# ME433_2017_1.net
KiCad netlist of a schematic drawn in EAGLE
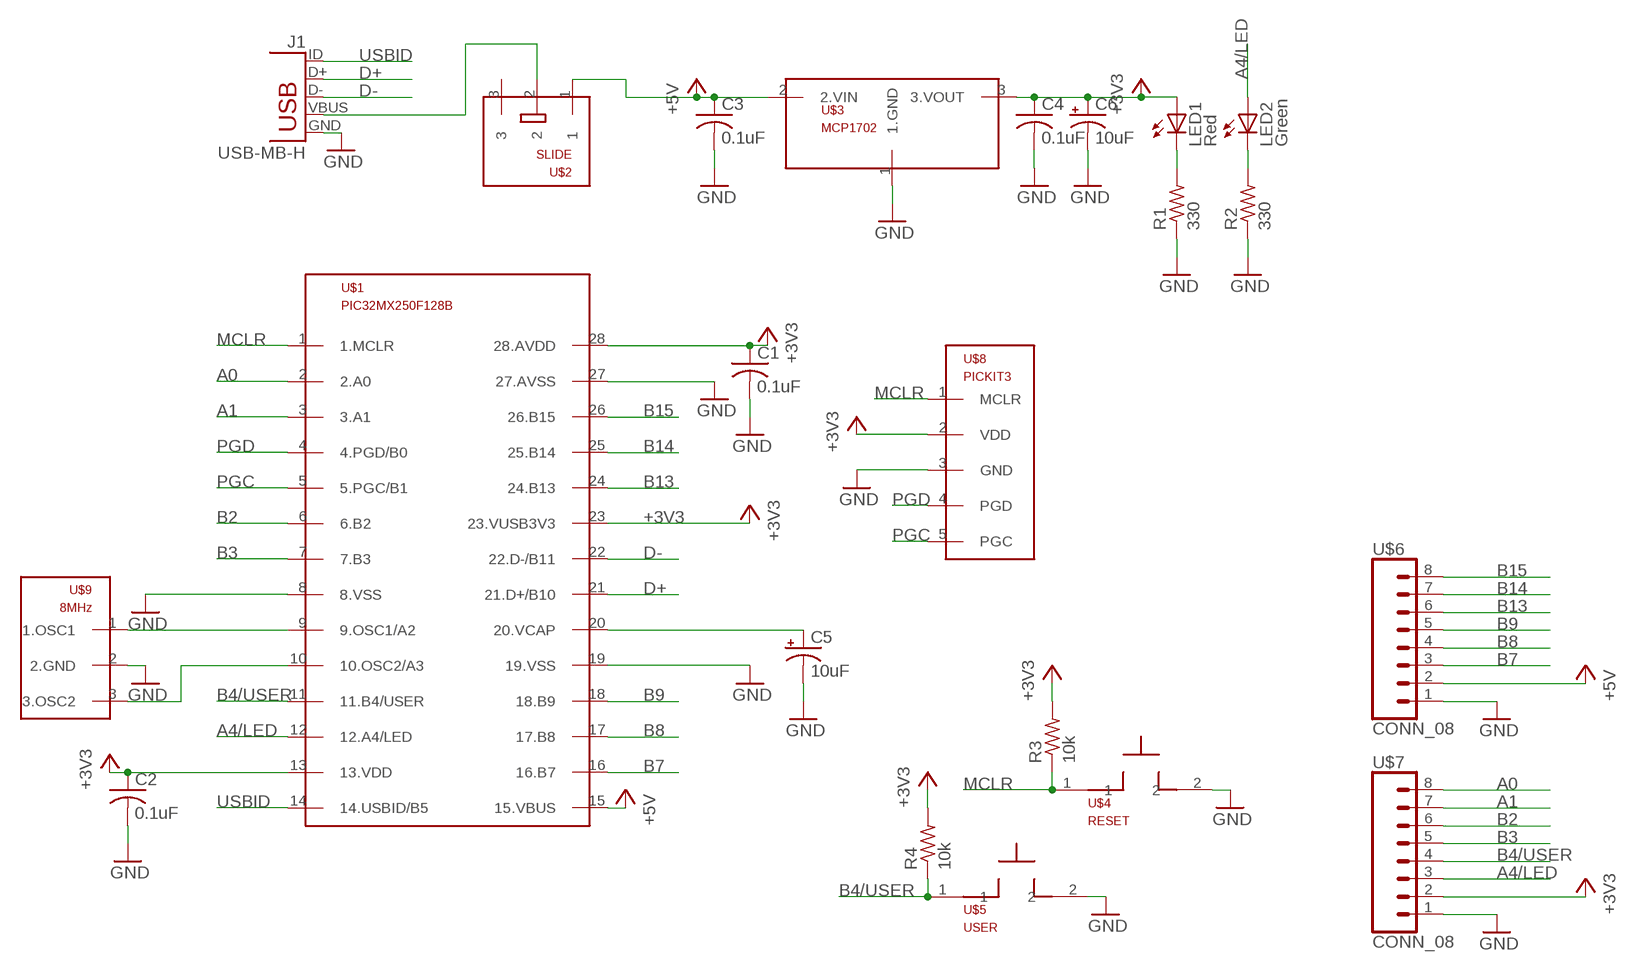
[diagram p0: schematic, sheet 1]

(export (version "E")
  (design (tool "Eeschema 10.0.6"))
  (components
    (comp (ref "C1")
      (value "0.1uF")
      (footprint "eagle-import:C025-025X050")
      (libsource (lib "eagle-import") (part "C-US025-025X050"))
    )
    (comp (ref "C2")
      (value "0.1uF")
      (footprint "eagle-import:C025-025X050")
      (libsource (lib "eagle-import") (part "C-US025-025X050"))
    )
    (comp (ref "C3")
      (value "0.1uF")
      (footprint "eagle-import:C025-025X050")
      (libsource (lib "eagle-import") (part "C-US025-025X050"))
    )
    (comp (ref "C4")
      (value "0.1uF")
      (footprint "eagle-import:C025-025X050")
      (libsource (lib "eagle-import") (part "C-US025-025X050"))
    )
    (comp (ref "C5")
      (value "10uF")
      (footprint "eagle-import:B45181B")
      (libsource (lib "eagle-import") (part "CPOL-USB45181B"))
    )
    (comp (ref "C6")
      (value "10uF")
      (footprint "eagle-import:B45181B")
      (libsource (lib "eagle-import") (part "CPOL-USB45181B"))
    )
    (comp (ref "J1")
      (value "USB-MB-H")
      (footprint "eagle-import:USB-MB-H")
      (libsource (lib "eagle-import") (part "USB-MB-H"))
    )
    (comp (ref "LED1")
      (value "Red")
      (footprint "eagle-import:LED3MM")
      (libsource (lib "eagle-import") (part "LED3MM"))
    )
    (comp (ref "LED2")
      (value "Green")
      (footprint "eagle-import:LED3MM")
      (libsource (lib "eagle-import") (part "LED3MM"))
    )
    (comp (ref "R1")
      (value "330")
      (footprint "eagle-import:0207_10")
      (libsource (lib "eagle-import") (part "R-US_0207/10"))
    )
    (comp (ref "R2")
      (value "330")
      (footprint "eagle-import:0207_10")
      (libsource (lib "eagle-import") (part "R-US_0207/10"))
    )
    (comp (ref "R3")
      (value "10k")
      (footprint "eagle-import:0207_10")
      (libsource (lib "eagle-import") (part "R-US_0207/10"))
    )
    (comp (ref "R4")
      (value "10k")
      (footprint "eagle-import:0207_10")
      (libsource (lib "eagle-import") (part "R-US_0207/10"))
    )
    (comp (ref "U$1")
      (value "PIC32MX250F128B")
      (footprint "eagle-import:DIL28-3")
      (libsource (lib "eagle-import") (part "PIC32MX250F128B"))
    )
    (comp (ref "U$2")
      (value "SLIDE")
      (footprint "eagle-import:SLIDE")
      (libsource (lib "eagle-import") (part "SLIDE"))
    )
    (comp (ref "U$3")
      (value "MCP1702")
      (footprint "eagle-import:TO92")
      (libsource (lib "eagle-import") (part "MCP1702"))
    )
    (comp (ref "U$4")
      (value "RESET")
      (footprint "eagle-import:PB")
      (libsource (lib "eagle-import") (part "PB"))
    )
    (comp (ref "U$5")
      (value "USER")
      (footprint "eagle-import:PB")
      (libsource (lib "eagle-import") (part "PB"))
    )
    (comp (ref "U$6")
      (value "CONN_08")
      (footprint "eagle-import:1X08")
      (libsource (lib "eagle-import") (part "CONN_08"))
    )
    (comp (ref "U$7")
      (value "CONN_08")
      (footprint "eagle-import:1X08")
      (libsource (lib "eagle-import") (part "CONN_08"))
    )
    (comp (ref "U$8")
      (value "PICKIT3")
      (footprint "eagle-import:1X05")
      (libsource (lib "eagle-import") (part "PICKIT3"))
    )
    (comp (ref "U$9")
      (value "8MHz")
      (footprint "eagle-import:OSC")
      (libsource (lib "eagle-import") (part "OSC"))
    )
  )
  (nets
    (net (code "1") (name "+3V3") (class "Default")
      (node (ref "C1") (pin "1") (pinfunction "1_1") (pintype "passive"))
      (node (ref "C2") (pin "1") (pinfunction "1_1") (pintype "passive"))
      (node (ref "C4") (pin "1") (pinfunction "1_1") (pintype "passive"))
      (node (ref "C6") (pin "+") (pinfunction "+_+") (pintype "passive"))
      (node (ref "LED1") (pin "A") (pinfunction "A_A") (pintype "passive"))
      (node (ref "R3") (pin "2") (pinfunction "2_2") (pintype "passive"))
      (node (ref "R4") (pin "2") (pinfunction "2_2") (pintype "passive"))
      (node (ref "U$1") (pin "13") (pinfunction "13.VDD_13") (pintype "bidirectional"))
      (node (ref "U$1") (pin "23") (pinfunction "23.VUSB3V3_23") (pintype "bidirectional"))
      (node (ref "U$1") (pin "28") (pinfunction "28.AVDD_28") (pintype "bidirectional"))
      (node (ref "U$3") (pin "3") (pinfunction "3.VOUT_3") (pintype "bidirectional"))
      (node (ref "U$7") (pin "2") (pinfunction "2_2") (pintype "passive"))
      (node (ref "U$8") (pin "2") (pinfunction "VDD_2") (pintype "bidirectional"))
    )
    (net (code "2") (name "+5V") (class "Default")
      (node (ref "C3") (pin "1") (pinfunction "1_1") (pintype "passive"))
      (node (ref "U$1") (pin "15") (pinfunction "15.VBUS_15") (pintype "bidirectional"))
      (node (ref "U$2") (pin "1") (pinfunction "1_1") (pintype "bidirectional"))
      (node (ref "U$3") (pin "2") (pinfunction "2.VIN_2") (pintype "bidirectional"))
      (node (ref "U$6") (pin "2") (pinfunction "2_2") (pintype "passive"))
    )
    (net (code "3") (name "/A0") (class "Default")
      (node (ref "U$1") (pin "2") (pinfunction "2.A0_2") (pintype "bidirectional"))
      (node (ref "U$7") (pin "8") (pinfunction "8_8") (pintype "passive"))
    )
    (net (code "4") (name "/A1") (class "Default")
      (node (ref "U$1") (pin "3") (pinfunction "3.A1_3") (pintype "bidirectional"))
      (node (ref "U$7") (pin "7") (pinfunction "7_7") (pintype "passive"))
    )
    (net (code "5") (name "/A4{slash}LED") (class "Default")
      (node (ref "LED2") (pin "A") (pinfunction "A_A") (pintype "passive"))
      (node (ref "U$1") (pin "12") (pinfunction "12.A4/LED_12") (pintype "bidirectional"))
      (node (ref "U$7") (pin "3") (pinfunction "3_3") (pintype "passive"))
    )
    (net (code "6") (name "/B2") (class "Default")
      (node (ref "U$1") (pin "6") (pinfunction "6.B2_6") (pintype "bidirectional"))
      (node (ref "U$7") (pin "6") (pinfunction "6_6") (pintype "passive"))
    )
    (net (code "7") (name "/B3") (class "Default")
      (node (ref "U$1") (pin "7") (pinfunction "7.B3_7") (pintype "bidirectional"))
      (node (ref "U$7") (pin "5") (pinfunction "5_5") (pintype "passive"))
    )
    (net (code "8") (name "/B4{slash}USER") (class "Default")
      (node (ref "R4") (pin "1") (pinfunction "1_1") (pintype "passive"))
      (node (ref "U$1") (pin "11") (pinfunction "11.B4/USER_11") (pintype "bidirectional"))
      (node (ref "U$5") (pin "1") (pinfunction "1_1") (pintype "bidirectional"))
      (node (ref "U$7") (pin "4") (pinfunction "4_4") (pintype "passive"))
    )
    (net (code "9") (name "/B7") (class "Default")
      (node (ref "U$1") (pin "16") (pinfunction "16.B7_16") (pintype "bidirectional"))
      (node (ref "U$6") (pin "3") (pinfunction "3_3") (pintype "passive"))
    )
    (net (code "10") (name "/B8") (class "Default")
      (node (ref "U$1") (pin "17") (pinfunction "17.B8_17") (pintype "bidirectional"))
      (node (ref "U$6") (pin "4") (pinfunction "4_4") (pintype "passive"))
    )
    (net (code "11") (name "/B9") (class "Default")
      (node (ref "U$1") (pin "18") (pinfunction "18.B9_18") (pintype "bidirectional"))
      (node (ref "U$6") (pin "5") (pinfunction "5_5") (pintype "passive"))
    )
    (net (code "12") (name "/B13") (class "Default")
      (node (ref "U$1") (pin "24") (pinfunction "24.B13_24") (pintype "bidirectional"))
      (node (ref "U$6") (pin "6") (pinfunction "6_6") (pintype "passive"))
    )
    (net (code "13") (name "/B14") (class "Default")
      (node (ref "U$1") (pin "25") (pinfunction "25.B14_25") (pintype "bidirectional"))
      (node (ref "U$6") (pin "7") (pinfunction "7_7") (pintype "passive"))
    )
    (net (code "14") (name "/B15") (class "Default")
      (node (ref "U$1") (pin "26") (pinfunction "26.B15_26") (pintype "bidirectional"))
      (node (ref "U$6") (pin "8") (pinfunction "8_8") (pintype "passive"))
    )
    (net (code "15") (name "/D+") (class "Default")
      (node (ref "J1") (pin "D+") (pinfunction "D+_D+") (pintype "bidirectional"))
      (node (ref "U$1") (pin "21") (pinfunction "21.D+/B10_21") (pintype "bidirectional"))
    )
    (net (code "16") (name "/D-") (class "Default")
      (node (ref "J1") (pin "D-") (pinfunction "D-_D-") (pintype "bidirectional"))
      (node (ref "U$1") (pin "22") (pinfunction "22.D-/B11_22") (pintype "bidirectional"))
    )
    (net (code "17") (name "/MCLR") (class "Default")
      (node (ref "R3") (pin "1") (pinfunction "1_1") (pintype "passive"))
      (node (ref "U$1") (pin "1") (pinfunction "1.MCLR_1") (pintype "bidirectional"))
      (node (ref "U$4") (pin "1") (pinfunction "1_1") (pintype "bidirectional"))
      (node (ref "U$8") (pin "1") (pinfunction "MCLR_1") (pintype "bidirectional"))
    )
    (net (code "18") (name "/PGC") (class "Default")
      (node (ref "U$1") (pin "5") (pinfunction "5.PGC/B1_5") (pintype "bidirectional"))
      (node (ref "U$8") (pin "5") (pinfunction "PGC_5") (pintype "bidirectional"))
    )
    (net (code "19") (name "/PGD") (class "Default")
      (node (ref "U$1") (pin "4") (pinfunction "4.PGD/B0_4") (pintype "bidirectional"))
      (node (ref "U$8") (pin "4") (pinfunction "PGD_4") (pintype "bidirectional"))
    )
    (net (code "20") (name "/USBID") (class "Default")
      (node (ref "J1") (pin "ID") (pinfunction "ID_ID") (pintype "bidirectional"))
      (node (ref "U$1") (pin "14") (pinfunction "14.USBID/B5_14") (pintype "bidirectional"))
    )
    (net (code "21") (name "GND") (class "Default")
      (node (ref "C1") (pin "2") (pinfunction "2_2") (pintype "passive"))
      (node (ref "C2") (pin "2") (pinfunction "2_2") (pintype "passive"))
      (node (ref "C3") (pin "2") (pinfunction "2_2") (pintype "passive"))
      (node (ref "C4") (pin "2") (pinfunction "2_2") (pintype "passive"))
      (node (ref "C5") (pin "-") (pinfunction "-_-") (pintype "passive"))
      (node (ref "C6") (pin "-") (pinfunction "-_-") (pintype "passive"))
      (node (ref "J1") (pin "GND") (pinfunction "GND_GND") (pintype "bidirectional"))
      (node (ref "R1") (pin "1") (pinfunction "1_1") (pintype "passive"))
      (node (ref "R2") (pin "1") (pinfunction "1_1") (pintype "passive"))
      (node (ref "U$1") (pin "19") (pinfunction "19.VSS_19") (pintype "bidirectional"))
      (node (ref "U$1") (pin "27") (pinfunction "27.AVSS_27") (pintype "bidirectional"))
      (node (ref "U$1") (pin "8") (pinfunction "8.VSS_8") (pintype "bidirectional"))
      (node (ref "U$3") (pin "1") (pinfunction "1.GND_1") (pintype "bidirectional"))
      (node (ref "U$4") (pin "2") (pinfunction "2_2") (pintype "bidirectional"))
      (node (ref "U$5") (pin "2") (pinfunction "2_2") (pintype "bidirectional"))
      (node (ref "U$6") (pin "1") (pinfunction "1_1") (pintype "passive"))
      (node (ref "U$7") (pin "1") (pinfunction "1_1") (pintype "passive"))
      (node (ref "U$8") (pin "3") (pinfunction "GND_3") (pintype "bidirectional"))
      (node (ref "U$9") (pin "2") (pinfunction "2.GND_2") (pintype "bidirectional"))
    )
    (net (code "22") (name "Net-(J1-PadVBUS)") (class "Default")
      (node (ref "J1") (pin "VBUS") (pinfunction "VBUS_VBUS") (pintype "bidirectional"))
      (node (ref "U$2") (pin "2") (pinfunction "2_2") (pintype "bidirectional"))
    )
    (net (code "23") (name "Net-(LED1-C)") (class "Default")
      (node (ref "LED1") (pin "K") (pinfunction "C_K") (pintype "passive"))
      (node (ref "R1") (pin "2") (pinfunction "2_2") (pintype "passive"))
    )
    (net (code "24") (name "Net-(LED2-C)") (class "Default")
      (node (ref "LED2") (pin "K") (pinfunction "C_K") (pintype "passive"))
      (node (ref "R2") (pin "2") (pinfunction "2_2") (pintype "passive"))
    )
    (net (code "25") (name "Net-(U$1-9.OSC1{slash}A2)") (class "Default")
      (node (ref "U$1") (pin "9") (pinfunction "9.OSC1/A2_9") (pintype "bidirectional"))
      (node (ref "U$9") (pin "1") (pinfunction "1.OSC1_1") (pintype "bidirectional"))
    )
    (net (code "26") (name "Net-(U$1-10.OSC2{slash}A3)") (class "Default")
      (node (ref "U$1") (pin "10") (pinfunction "10.OSC2/A3_10") (pintype "bidirectional"))
      (node (ref "U$9") (pin "3") (pinfunction "3.OSC2_3") (pintype "bidirectional"))
    )
    (net (code "27") (name "Net-(U$1-20.VCAP)") (class "Default")
      (node (ref "C5") (pin "+") (pinfunction "+_+") (pintype "passive"))
      (node (ref "U$1") (pin "20") (pinfunction "20.VCAP_20") (pintype "bidirectional"))
    )
    (net (code "28") (name "unconnected-(U$2-Pad3)") (class "Default")
      (node (ref "U$2") (pin "3") (pinfunction "3_3") (pintype "bidirectional"))
    )
  )
)
